# Data_Blue.net
KiCad netlist of a schematic drawn in Altium Designer
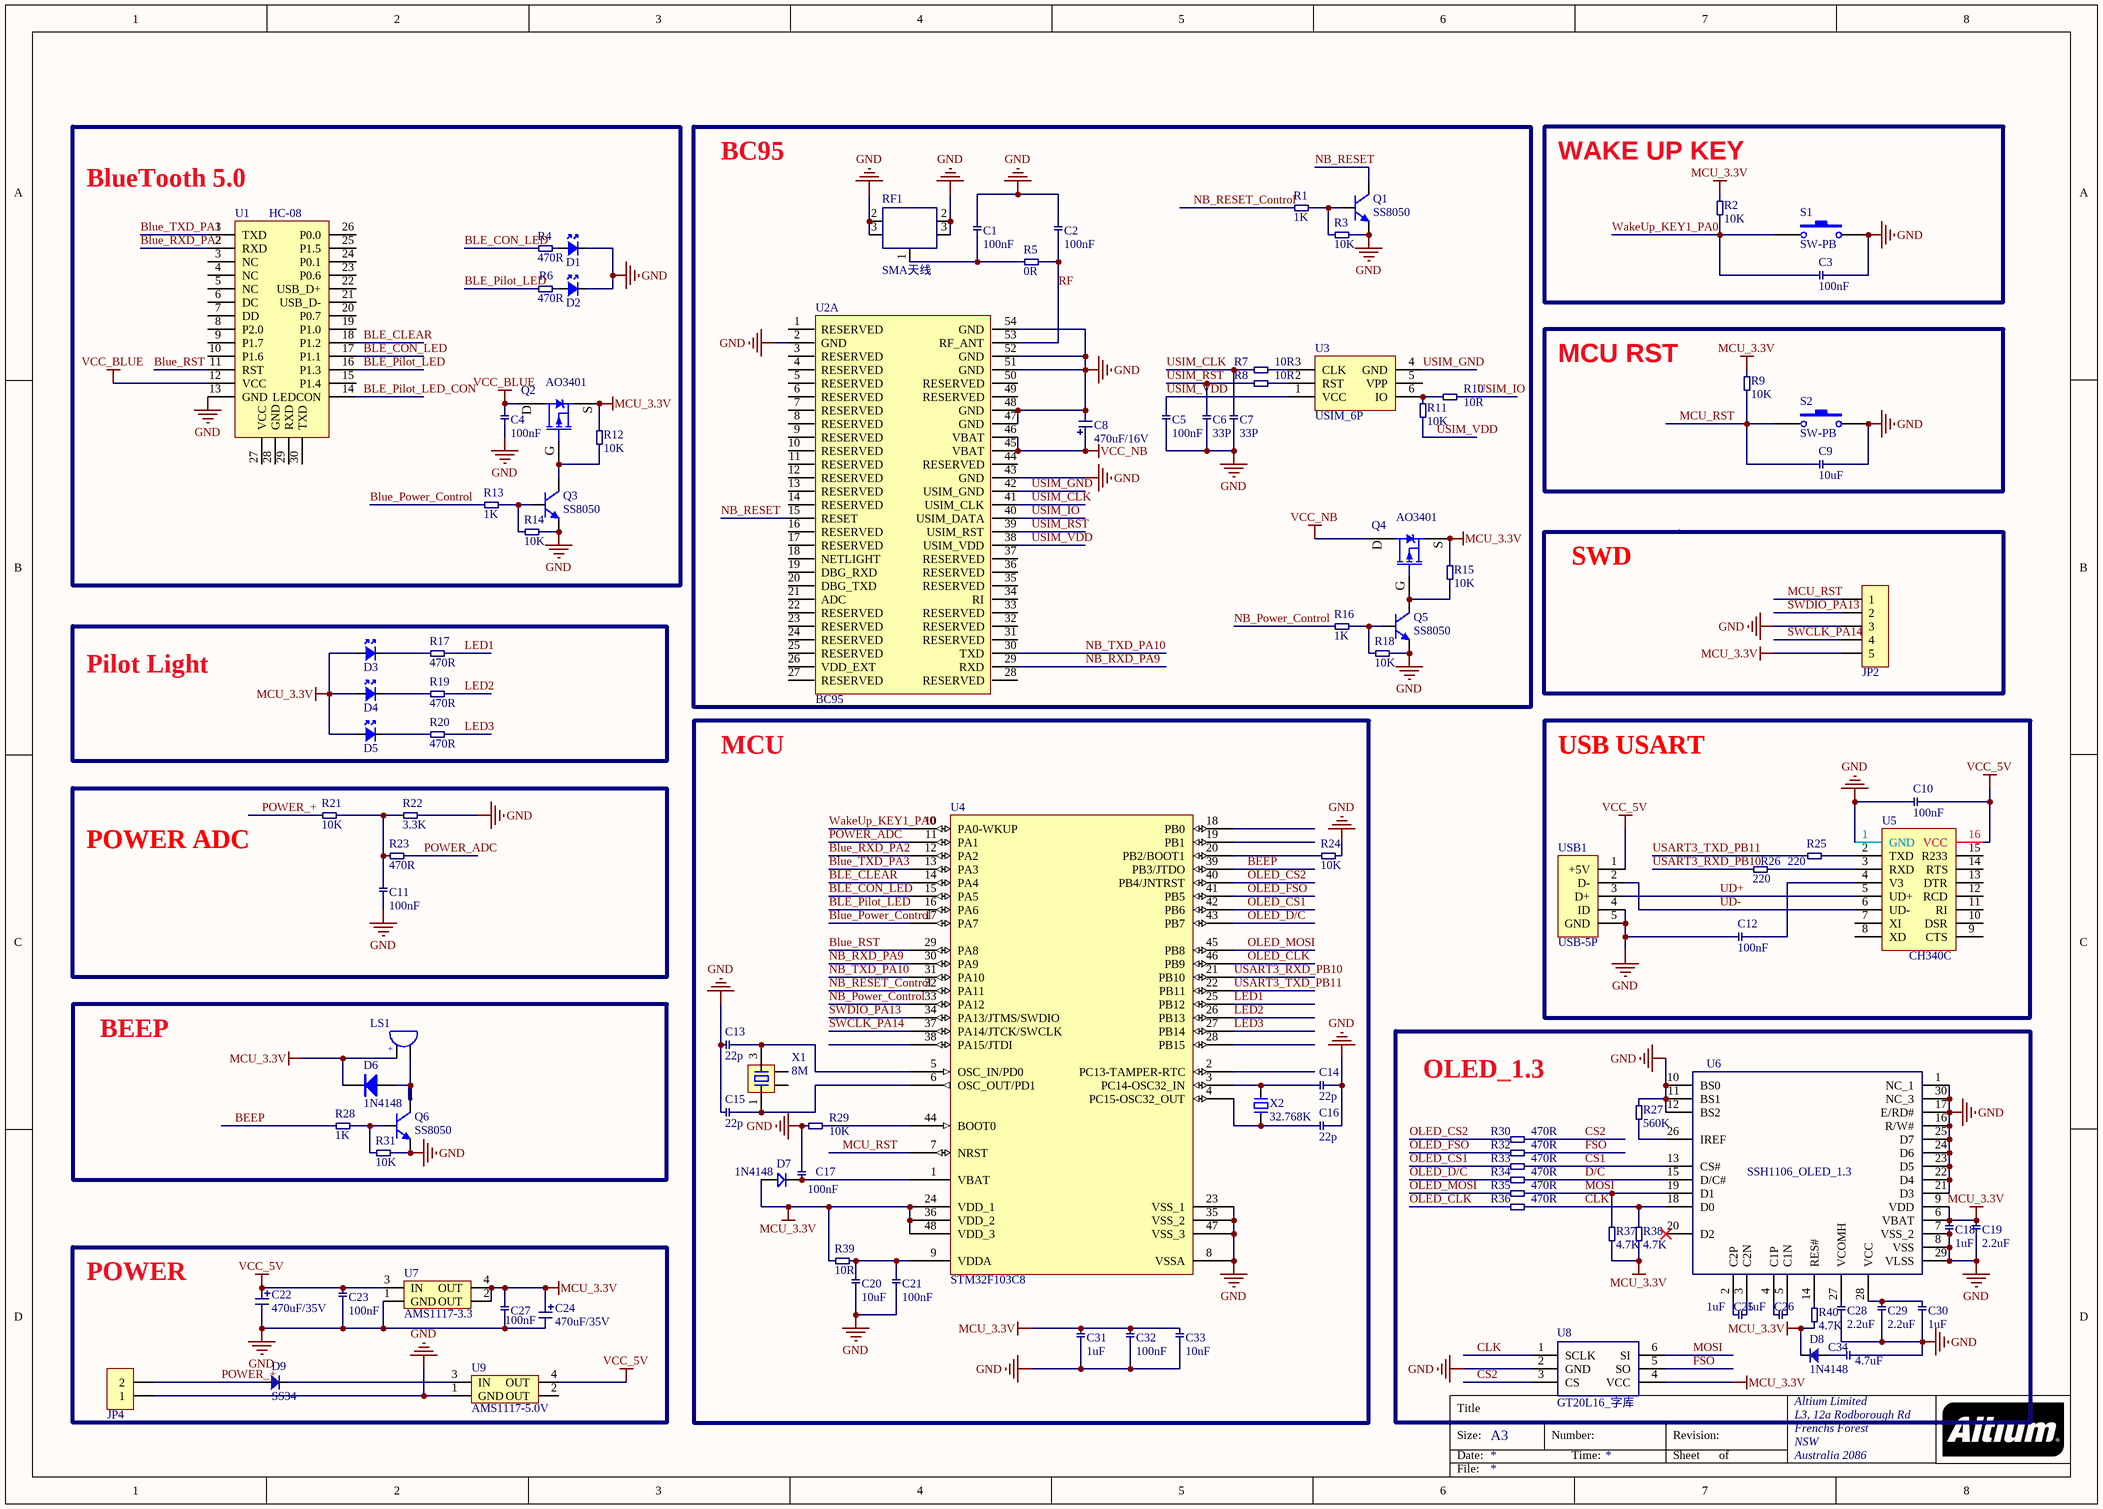
[diagram p0: Data_Blue.SchDoc]

(export (version "E")
  (design (tool "Eeschema 10.0.6"))
  (components
    (comp (ref "C1") (value "100nF") (footprint "0603CC") (libsource (lib "LFZ@WLP") (part "cap")))
    (comp (ref "C2") (value "100nF") (footprint "0603CC") (libsource (lib "LFZ@WLP") (part "cap")))
    (comp (ref "C3") (value "100nF") (footprint "0603CC") (libsource (lib "LFZ@WLP") (part "cap")))
    (comp (ref "C4") (value "100nF") (footprint "0603CC") (libsource (lib "LFZ@WLP") (part "cap")))
    (comp (ref "C5") (value "100nF") (footprint "0603CC") (libsource (lib "LFZ@WLP") (part "cap")))
    (comp (ref "C6") (value "33P") (footprint "0603CC") (libsource (lib "LFZ@WLP") (part "cap")))
    (comp (ref "C7") (value "33P") (footprint "0603CC") (libsource (lib "LFZ@WLP") (part "cap")))
    (comp (ref "C8") (value "470uF/16V") (footprint "C3216") (libsource (lib "LFZ@WLP") (part "Ecap")))
    (comp (ref "C9") (value "10uF") (footprint "0603CC") (libsource (lib "LFZ@WLP") (part "cap")))
    (comp (ref "C10") (value "100nF") (footprint "0603CC") (libsource (lib "LFZ@WLP") (part "cap")))
    (comp (ref "C11") (value "100nF") (footprint "0603CC") (libsource (lib "LFZ@WLP") (part "cap")))
    (comp (ref "C12") (value "100nF") (footprint "0603CC") (libsource (lib "LFZ@WLP") (part "cap")))
    (comp (ref "C13") (value "22p") (footprint "0603CC") (libsource (lib "LFZ@WLP") (part "cap")))
    (comp (ref "C14") (value "22p") (footprint "0603CC") (libsource (lib "LFZ@WLP") (part "cap")))
    (comp (ref "C15") (value "22p") (footprint "0603CC") (libsource (lib "LFZ@WLP") (part "cap")))
    (comp (ref "C16") (value "22p") (footprint "0603CC") (libsource (lib "LFZ@WLP") (part "cap")))
    (comp (ref "C17") (value "100nF") (footprint "0603CC") (libsource (lib "LFZ@WLP") (part "cap")))
    (comp (ref "C18") (value "1uF") (footprint "0603CC") (libsource (lib "LFZ@WLP") (part "cap")))
    (comp (ref "C19") (value "2.2uF") (footprint "0603CC") (libsource (lib "LFZ@WLP") (part "cap")))
    (comp (ref "C20") (value "10uF") (footprint "0603CC") (libsource (lib "LFZ@WLP") (part "cap")))
    (comp (ref "C21") (value "100nF") (footprint "0603CC") (libsource (lib "LFZ@WLP") (part "cap")))
    (comp (ref "C22") (value "470uF/35V") (footprint "CD A(3216)") (libsource (lib "LFZ@WLP") (part "Ecap")))
    (comp (ref "C23") (value "100nF") (footprint "0603CC") (libsource (lib "LFZ@WLP") (part "cap")))
    (comp (ref "C24") (value "470uF/35V") (footprint "C3216") (libsource (lib "LFZ@WLP") (part "Ecap")))
    (comp (ref "C25") (value "1uF") (footprint "0603CC") (libsource (lib "LFZ@WLP") (part "cap")))
    (comp (ref "C26") (value "1uF") (footprint "0603CC") (libsource (lib "LFZ@WLP") (part "cap")))
    (comp (ref "C27") (value "100nF") (footprint "0603CC") (libsource (lib "LFZ@WLP") (part "cap")))
    (comp (ref "C28") (value "2.2uF") (footprint "0603CC") (libsource (lib "LFZ@WLP") (part "cap")))
    (comp (ref "C29") (value "2.2uF") (footprint "0603CC") (libsource (lib "LFZ@WLP") (part "cap")))
    (comp (ref "C30") (value "1uF") (footprint "0603CC") (libsource (lib "LFZ@WLP") (part "cap")))
    (comp (ref "C31") (value "1uF") (footprint "0603CC") (libsource (lib "LFZ@WLP") (part "cap")))
    (comp (ref "C32") (value "100nF") (footprint "0603CC") (libsource (lib "LFZ@WLP") (part "cap")))
    (comp (ref "C33") (value "10nF") (footprint "0603CC") (libsource (lib "LFZ@WLP") (part "cap")))
    (comp (ref "C34") (value "4.7uF") (footprint "0603CC") (libsource (lib "LFZ@WLP") (part "cap")))
    (comp (ref "D1") (value "LED") (footprint "LED 0603G") (libsource (lib "LFZ@WLP") (part "LED")))
    (comp (ref "D2") (value "LED") (footprint "LED 0603R") (libsource (lib "LFZ@WLP") (part "LED")))
    (comp (ref "D3") (value "LED") (footprint "LED 3MM-G") (libsource (lib "LFZ@WLP") (part "LED")))
    (comp (ref "D4") (value "LED") (footprint "LED 3MM-G") (libsource (lib "LFZ@WLP") (part "LED")))
    (comp (ref "D5") (value "LED") (footprint "LED 3MM-G") (libsource (lib "LFZ@WLP") (part "LED")))
    (comp (ref "D6")
      (value "1N4148")
      (footprint "SOD-323")
      (description "高速开关二极管")
      (libsource (lib "8.1   - 二极管-整流桥") (part "1N4148"))
    )
    (comp (ref "D7")
      (value "1N4148")
      (footprint "SOD-323")
      (libsource (lib "WarShip V3 STM32103封装库") (part "D"))
    )
    (comp (ref "D8") (value "1N4148") (footprint "SOD-523") (libsource (lib "LFZ@WLP") (part "Diod")))
    (comp (ref "D9") (value "SS34") (footprint "SMA") (libsource (lib "Diod") (part "Diod")))
    (comp (ref "JP2")
      (value "HDR-1X5")
      (footprint "HDR2.54-LI-5P")
      (description "5P接插件")
      (libsource (lib "4.5   - 接插件-脚距2.54") (part "Header 5"))
    )
    (comp (ref "JP4")
      (value "HDR-1X2")
      (footprint "XH2.54-WI-2P")
      (description "2P接插件")
      (libsource (lib "4.5   - 接插件-脚距2.54") (part "Header 2"))
    )
    (comp (ref "LS1")
      (value "DC5V")
      (footprint "BEEP 5x9x5.5")
      (description "蜂鸣器")
      (libsource (lib "15.1 - 未分类器件") (part "BEEP"))
    )
    (comp (ref "Q1")
      (value "SS8050")
      (footprint "SOT23-3N")
      (description "高频放大-NPN型")
      (libsource (lib "6.2   - 三极管") (part "8050-SMD"))
    )
    (comp (ref "Q2")
      (value "AO3401")
      (footprint "SOT23-3N")
      (description "P沟道场效应管")
      (libsource (lib "6.1   - 场效应管-可控硅") (part "SI2301"))
    )
    (comp (ref "Q3")
      (value "SS8050")
      (footprint "SOT23-3N")
      (description "高频放大-NPN型")
      (libsource (lib "6.2   - 三极管") (part "8050-SMD"))
    )
    (comp (ref "Q4")
      (value "AO3401")
      (footprint "SOT23-3N")
      (description "P沟道场效应管")
      (libsource (lib "6.1   - 场效应管-可控硅") (part "SI2301"))
    )
    (comp (ref "Q5")
      (value "SS8050")
      (footprint "SOT23-3N")
      (description "高频放大-NPN型")
      (libsource (lib "6.2   - 三极管") (part "8050-SMD"))
    )
    (comp (ref "Q6")
      (value "SS8050")
      (footprint "SOT23-3N")
      (description "高频放大-NPN型")
      (libsource (lib "6.2   - 三极管") (part "8050-SMD"))
    )
    (comp (ref "R1") (value "1K") (footprint "0603RR") (libsource (lib "LFZ@WLP") (part "res")))
    (comp (ref "R2") (value "10K") (footprint "0603RR") (libsource (lib "LFZ@WLP") (part "res")))
    (comp (ref "R3") (value "10K") (footprint "0603RR") (libsource (lib "LFZ@WLP") (part "res")))
    (comp (ref "R4") (value "470R") (footprint "0603RR") (libsource (lib "LFZ@WLP") (part "res")))
    (comp (ref "R5") (value "0R") (footprint "0603RR") (libsource (lib "LFZ@WLP") (part "res")))
    (comp (ref "R6") (value "470R") (footprint "0603RR") (libsource (lib "LFZ@WLP") (part "res")))
    (comp (ref "R7") (value "10R") (footprint "0603RR") (libsource (lib "LFZ@WLP") (part "res")))
    (comp (ref "R8") (value "10R") (footprint "0603RR") (libsource (lib "LFZ@WLP") (part "res")))
    (comp (ref "R9") (value "10K") (footprint "0603RR") (libsource (lib "LFZ@WLP") (part "res")))
    (comp (ref "R10") (value "10R") (footprint "0603RR") (libsource (lib "LFZ@WLP") (part "res")))
    (comp (ref "R11") (value "10K") (footprint "0603RR") (libsource (lib "LFZ@WLP") (part "res")))
    (comp (ref "R12") (value "10K") (footprint "0603RR") (libsource (lib "LFZ@WLP") (part "res")))
    (comp (ref "R13") (value "1K") (footprint "0603RR") (libsource (lib "LFZ@WLP") (part "res")))
    (comp (ref "R14") (value "10K") (footprint "0603RR") (libsource (lib "LFZ@WLP") (part "res")))
    (comp (ref "R15") (value "10K") (footprint "0603RR") (libsource (lib "LFZ@WLP") (part "res")))
    (comp (ref "R16") (value "1K") (footprint "0603RR") (libsource (lib "LFZ@WLP") (part "res")))
    (comp (ref "R17") (value "470R") (footprint "0603RR") (libsource (lib "LFZ@WLP") (part "res")))
    (comp (ref "R18") (value "10K") (footprint "0603RR") (libsource (lib "LFZ@WLP") (part "res")))
    (comp (ref "R19") (value "470R") (footprint "0603RR") (libsource (lib "LFZ@WLP") (part "res")))
    (comp (ref "R20") (value "470R") (footprint "0603RR") (libsource (lib "LFZ@WLP") (part "res")))
    (comp (ref "R21") (value "10K") (footprint "0603RR") (libsource (lib "LFZ@WLP") (part "res")))
    (comp (ref "R22") (value "3.3K") (footprint "0603RR") (libsource (lib "LFZ@WLP") (part "res")))
    (comp (ref "R23") (value "470R") (footprint "0603RR") (libsource (lib "LFZ@WLP") (part "res")))
    (comp (ref "R24") (value "10K") (footprint "0603RR") (libsource (lib "LFZ@WLP") (part "res")))
    (comp (ref "R25") (value "220") (footprint "0603RR") (libsource (lib "LFZ@WLP") (part "res")))
    (comp (ref "R26") (value "220") (footprint "0603RR") (libsource (lib "LFZ@WLP") (part "res")))
    (comp (ref "R27") (value "560K") (footprint "0603RR") (libsource (lib "LFZ@WLP") (part "res")))
    (comp (ref "R28") (value "1K") (footprint "0603RR") (libsource (lib "LFZ@WLP") (part "res")))
    (comp (ref "R29") (value "10K") (footprint "0603RR") (libsource (lib "LFZ@WLP") (part "res")))
    (comp (ref "R30") (value "470R") (footprint "0603RR") (libsource (lib "LFZ@WLP") (part "res")))
    (comp (ref "R31") (value "10K") (footprint "0603RR") (libsource (lib "LFZ@WLP") (part "res")))
    (comp (ref "R32") (value "470R") (footprint "0603RR") (libsource (lib "LFZ@WLP") (part "res")))
    (comp (ref "R33") (value "470R") (footprint "0603RR") (libsource (lib "LFZ@WLP") (part "res")))
    (comp (ref "R34") (value "470R") (footprint "0603RR") (libsource (lib "LFZ@WLP") (part "res")))
    (comp (ref "R35") (value "470R") (footprint "0603RR") (libsource (lib "LFZ@WLP") (part "res")))
    (comp (ref "R36") (value "470R") (footprint "0603RR") (libsource (lib "LFZ@WLP") (part "res")))
    (comp (ref "R37") (value "4.7K") (footprint "0603RR") (libsource (lib "LFZ@WLP") (part "res")))
    (comp (ref "R38") (value "4.7K") (footprint "0603RR") (libsource (lib "LFZ@WLP") (part "res")))
    (comp (ref "R39") (value "10R") (footprint "0603RR") (libsource (lib "LFZ@WLP") (part "res")))
    (comp (ref "R40") (value "4.7K") (footprint "0603RR") (libsource (lib "LFZ@WLP") (part "res")))
    (comp (ref "RF1") (value "SMA天线") (footprint "SMA_FR") (libsource (lib "LFZ@WLP") (part "SMA天线")))
    (comp (ref "S1")
      (value "SW-PB")
      (footprint "TSW SMD-6*6*6")
      (description "Switch")
      (libsource (lib "开关及电源") (part "SW-PB"))
    )
    (comp (ref "S2")
      (value "SW-PB")
      (footprint "TSW SMD-4*4*1.5")
      (description "Switch")
      (libsource (lib "开关及电源") (part "SW-PB"))
    )
    (comp (ref "U1") (value "HC-08") (footprint "HC-08") (libsource (lib "LFZ@WLP") (part "HC-08")))
    (comp (ref "U2")
      (value "BC95")
      (footprint "BC95")
      (libsource (lib "Quectel_BC95_SCH_Part_Protel&AD_20170925") (part "BC95"))
    )
    (comp (ref "U3") (value "USIM_6P") (footprint "SIM 6P 自弹") (libsource (lib "XG-BM02") (part "USIM-6P")))
    (comp (ref "U4")
      (value "STM32F103C8")
      (footprint "LQFP48 7X7_M")
      (description "Flaah:64/RAM:20/IO:36")
      (libsource (lib "2.1   - STM32系列单片机") (part "STM32F103C8"))
    )
    (comp (ref "U5") (value "CH340C") (footprint "SOP16_L") (libsource (lib "LFZ@WLP") (part "CH340C")))
    (comp (ref "U6")
      (value "SSH1106_OLED_1.3")
      (footprint "OLED_1.3_FPC_30")
      (libsource (lib "LFZ@WLP") (part "SSH1106_OLED_1.3"))
    )
    (comp (ref "U7")
      (value "AMS1117-3.3")
      (footprint "SOT223_N")
      (libsource (lib "WarShip V3 STM32103封装库") (part "AMS1117"))
    )
    (comp (ref "U8")
      (value "GT20L16_字库")
      (footprint "SOT23-6")
      (libsource (lib "LFZ@WLP") (part "GT20L16_字库"))
    )
    (comp (ref "U9")
      (value "AMS1117-5.0V")
      (footprint "SOT223_N")
      (libsource (lib "WarShip V3 STM32103封装库") (part "AMS1117"))
    )
    (comp (ref "USB1")
      (value "USB-5P")
      (footprint "USB-MICRO_A")
      (description "微型USB母座")
      (libsource (lib "4.1   - 接口类") (part "USB-5P"))
    )
    (comp (ref "X1")
      (value "8M")
      (footprint "OSC 3225-4P")
      (description "4脚无源晶振")
      (libsource (lib "10.1 - 保险丝-晶振") (part "XTAL-4P"))
    )
    (comp (ref "X2")
      (value "32.768K")
      (footprint "OSC 3215-2P")
      (description "2脚无源脚晶振")
      (libsource (lib "10.1 - 保险丝-晶振") (part "XTAL-2P"))
    )
  )
  (nets
    (net (code "1") (name "/BEEP") (class "Default")
      (node (ref "R28") (pin "1") (pinfunction "1_1") (pintype "passive"))
      (node (ref "U4") (pin "39") (pinfunction "PB3/JTDO_39") (pintype "bidirectional"))
    )
    (net (code "2") (name "/BLE_CLEAR") (class "Default")
      (node (ref "U1") (pin "18") (pinfunction "P1.2_18") (pintype "passive"))
      (node (ref "U4") (pin "14") (pinfunction "PA4_14") (pintype "bidirectional"))
    )
    (net (code "3") (name "/BLE_CON_LED") (class "Default")
      (node (ref "R4") (pin "1") (pinfunction "1_1") (pintype "passive"))
      (node (ref "U1") (pin "17") (pinfunction "P1.1_17") (pintype "passive"))
      (node (ref "U4") (pin "15") (pinfunction "PA5_15") (pintype "bidirectional"))
    )
    (net (code "4") (name "/BLE_Pilot_LED") (class "Default")
      (node (ref "R6") (pin "1") (pinfunction "1_1") (pintype "passive"))
      (node (ref "U1") (pin "16") (pinfunction "P1.3_16") (pintype "passive"))
      (node (ref "U4") (pin "16") (pinfunction "PA6_16") (pintype "bidirectional"))
    )
    (net (code "5") (name "/BLE_Pilot_LED_CON") (class "Default")
      (node (ref "U1") (pin "14") (pinfunction "LEDCON_14") (pintype "passive"))
    )
    (net (code "6") (name "/Blue_Power_Control") (class "Default")
      (node (ref "R13") (pin "1") (pinfunction "1_1") (pintype "passive"))
      (node (ref "U4") (pin "17") (pinfunction "PA7_17") (pintype "bidirectional"))
    )
    (net (code "7") (name "/Blue_RST") (class "Default")
      (node (ref "U1") (pin "11") (pinfunction "RST_11") (pintype "passive"))
      (node (ref "U4") (pin "29") (pinfunction "PA8_29") (pintype "bidirectional"))
    )
    (net (code "8") (name "/Blue_RXD_PA2") (class "Default")
      (node (ref "U1") (pin "2") (pinfunction "RXD_2") (pintype "passive"))
      (node (ref "U4") (pin "12") (pinfunction "PA2_12") (pintype "bidirectional"))
    )
    (net (code "9") (name "/Blue_TXD_PA3") (class "Default")
      (node (ref "U1") (pin "1") (pinfunction "TXD_1") (pintype "passive"))
      (node (ref "U4") (pin "13") (pinfunction "PA3_13") (pintype "bidirectional"))
    )
    (net (code "10") (name "/CLK") (class "Default")
      (node (ref "R36") (pin "2") (pinfunction "2_2") (pintype "passive"))
      (node (ref "R38") (pin "2") (pinfunction "2_2") (pintype "passive"))
      (node (ref "U6") (pin "18") (pinfunction "D0_18") (pintype "passive"))
      (node (ref "U8") (pin "1") (pinfunction "SCLK_1") (pintype "passive"))
    )
    (net (code "11") (name "/CS1") (class "Default")
      (node (ref "R33") (pin "2") (pinfunction "2_2") (pintype "passive"))
      (node (ref "U6") (pin "13") (pinfunction "CS#_13") (pintype "passive"))
    )
    (net (code "12") (name "/CS2") (class "Default")
      (node (ref "R30") (pin "2") (pinfunction "2_2") (pintype "passive"))
      (node (ref "U8") (pin "3") (pinfunction "CS_3") (pintype "passive"))
    )
    (net (code "13") (name "/D{slash}C") (class "Default")
      (node (ref "R34") (pin "2") (pinfunction "2_2") (pintype "passive"))
      (node (ref "U6") (pin "15") (pinfunction "D/C#_15") (pintype "passive"))
    )
    (net (code "14") (name "/FSO") (class "Default")
      (node (ref "R32") (pin "2") (pinfunction "2_2") (pintype "passive"))
      (node (ref "U8") (pin "5") (pinfunction "SO_5") (pintype "passive"))
    )
    (net (code "15") (name "/LED1") (class "Default")
      (node (ref "R17") (pin "2") (pinfunction "2_2") (pintype "passive"))
      (node (ref "U4") (pin "25") (pinfunction "PB12_25") (pintype "bidirectional"))
    )
    (net (code "16") (name "/LED2") (class "Default")
      (node (ref "R19") (pin "2") (pinfunction "2_2") (pintype "passive"))
      (node (ref "U4") (pin "26") (pinfunction "PB13_26") (pintype "bidirectional"))
    )
    (net (code "17") (name "/LED3") (class "Default")
      (node (ref "R20") (pin "2") (pinfunction "2_2") (pintype "passive"))
      (node (ref "U4") (pin "27") (pinfunction "PB14_27") (pintype "bidirectional"))
    )
    (net (code "18") (name "/MCU_RST") (class "Default")
      (node (ref "C9") (pin "2") (pinfunction "2_2") (pintype "passive"))
      (node (ref "JP2") (pin "1") (pinfunction "1_1") (pintype "passive"))
      (node (ref "R9") (pin "1") (pinfunction "1_1") (pintype "passive"))
      (node (ref "S2") (pin "1") (pinfunction "1_1") (pintype "passive"))
      (node (ref "U4") (pin "7") (pinfunction "NRST_7") (pintype "bidirectional"))
    )
    (net (code "19") (name "/MOSI") (class "Default")
      (node (ref "R35") (pin "2") (pinfunction "2_2") (pintype "passive"))
      (node (ref "R37") (pin "2") (pinfunction "2_2") (pintype "passive"))
      (node (ref "U6") (pin "19") (pinfunction "D1_19") (pintype "passive"))
      (node (ref "U8") (pin "6") (pinfunction "SI_6") (pintype "passive"))
    )
    (net (code "20") (name "/NB_Power_Control") (class "Default")
      (node (ref "R16") (pin "1") (pinfunction "1_1") (pintype "passive"))
      (node (ref "U4") (pin "33") (pinfunction "PA12_33") (pintype "bidirectional"))
    )
    (net (code "21") (name "/NB_RESET") (class "Default")
      (node (ref "Q1") (pin "3") (pinfunction "C_3") (pintype "passive"))
      (node (ref "U2") (pin "15") (pinfunction "RESET_15") (pintype "passive"))
    )
    (net (code "22") (name "/NB_RESET_Control") (class "Default")
      (node (ref "R1") (pin "1") (pinfunction "1_1") (pintype "passive"))
      (node (ref "U4") (pin "32") (pinfunction "PA11_32") (pintype "bidirectional"))
    )
    (net (code "23") (name "/NB_RXD_PA9") (class "Default")
      (node (ref "U2") (pin "29") (pinfunction "RXD_29") (pintype "passive"))
      (node (ref "U4") (pin "30") (pinfunction "PA9_30") (pintype "bidirectional"))
    )
    (net (code "24") (name "/NB_TXD_PA10") (class "Default")
      (node (ref "U2") (pin "30") (pinfunction "TXD_30") (pintype "passive"))
      (node (ref "U4") (pin "31") (pinfunction "PA10_31") (pintype "bidirectional"))
    )
    (net (code "25") (name "/OLED_CLK") (class "Default")
      (node (ref "R36") (pin "1") (pinfunction "1_1") (pintype "passive"))
      (node (ref "U4") (pin "46") (pinfunction "PB9_46") (pintype "bidirectional"))
    )
    (net (code "26") (name "/OLED_CS1") (class "Default")
      (node (ref "R33") (pin "1") (pinfunction "1_1") (pintype "passive"))
      (node (ref "U4") (pin "42") (pinfunction "PB6_42") (pintype "bidirectional"))
    )
    (net (code "27") (name "/OLED_CS2") (class "Default")
      (node (ref "R30") (pin "1") (pinfunction "1_1") (pintype "passive"))
      (node (ref "U4") (pin "40") (pinfunction "PB4/JNTRST_40") (pintype "bidirectional"))
    )
    (net (code "28") (name "/OLED_D{slash}C") (class "Default")
      (node (ref "R34") (pin "1") (pinfunction "1_1") (pintype "passive"))
      (node (ref "U4") (pin "43") (pinfunction "PB7_43") (pintype "bidirectional"))
    )
    (net (code "29") (name "/OLED_FSO") (class "Default")
      (node (ref "R32") (pin "1") (pinfunction "1_1") (pintype "passive"))
      (node (ref "U4") (pin "41") (pinfunction "PB5_41") (pintype "bidirectional"))
    )
    (net (code "30") (name "/OLED_MOSI") (class "Default")
      (node (ref "R35") (pin "1") (pinfunction "1_1") (pintype "passive"))
      (node (ref "U4") (pin "45") (pinfunction "PB8_45") (pintype "bidirectional"))
    )
    (net (code "31") (name "/POWER_+") (class "Default")
      (node (ref "D9") (pin "1") (pinfunction "ANODE_1") (pintype "passive"))
      (node (ref "JP4") (pin "2") (pinfunction "2_2") (pintype "passive"))
      (node (ref "R21") (pin "1") (pinfunction "1_1") (pintype "passive"))
    )
    (net (code "32") (name "/POWER_ADC") (class "Default")
      (node (ref "R23") (pin "1") (pinfunction "1_1") (pintype "passive"))
      (node (ref "U4") (pin "11") (pinfunction "PA1_11") (pintype "bidirectional"))
    )
    (net (code "33") (name "/RF") (class "Default")
      (node (ref "C2") (pin "1") (pinfunction "1_1") (pintype "passive"))
      (node (ref "R5") (pin "1") (pinfunction "1_1") (pintype "passive"))
      (node (ref "U2") (pin "53") (pinfunction "RF_ANT_53") (pintype "passive"))
    )
    (net (code "34") (name "/SWCLK_PA14") (class "Default")
      (node (ref "JP2") (pin "4") (pinfunction "4_4") (pintype "passive"))
      (node (ref "U4") (pin "37") (pinfunction "PA14/JTCK/SWCLK_37") (pintype "bidirectional"))
    )
    (net (code "35") (name "/SWDIO_PA13") (class "Default")
      (node (ref "JP2") (pin "2") (pinfunction "2_2") (pintype "passive"))
      (node (ref "U4") (pin "34") (pinfunction "PA13/JTMS/SWDIO_34") (pintype "bidirectional"))
    )
    (net (code "36") (name "/UD+") (class "Default")
      (node (ref "U5") (pin "5") (pinfunction "UD+_5") (pintype "passive"))
      (node (ref "USB1") (pin "3") (pinfunction "D+_3") (pintype "passive"))
    )
    (net (code "37") (name "/UD-") (class "Default")
      (node (ref "U5") (pin "6") (pinfunction "UD-_6") (pintype "passive"))
      (node (ref "USB1") (pin "2") (pinfunction "D-_2") (pintype "passive"))
    )
    (net (code "38") (name "/USART3_RXD_PB10") (class "Default")
      (node (ref "R26") (pin "1") (pinfunction "1_1") (pintype "passive"))
      (node (ref "U4") (pin "21") (pinfunction "PB10_21") (pintype "bidirectional"))
    )
    (net (code "39") (name "/USART3_TXD_PB11") (class "Default")
      (node (ref "R25") (pin "1") (pinfunction "1_1") (pintype "passive"))
      (node (ref "U4") (pin "22") (pinfunction "PB11_22") (pintype "bidirectional"))
    )
    (net (code "40") (name "/USIM_CLK") (class "Default")
      (node (ref "C7") (pin "2") (pinfunction "2_2") (pintype "passive"))
      (node (ref "R7") (pin "1") (pinfunction "1_1") (pintype "passive"))
      (node (ref "U2") (pin "41") (pinfunction "USIM_CLK_41") (pintype "passive"))
    )
    (net (code "41") (name "/USIM_GND") (class "Default")
      (node (ref "U2") (pin "42") (pinfunction "USIM_GND_42") (pintype "passive"))
      (node (ref "U3") (pin "4") (pinfunction "GND_4") (pintype "passive"))
    )
    (net (code "42") (name "/USIM_IO") (class "Default")
      (node (ref "R10") (pin "1") (pinfunction "1_1") (pintype "passive"))
      (node (ref "U2") (pin "40") (pinfunction "USIM_DATA_40") (pintype "passive"))
    )
    (net (code "43") (name "/USIM_RST") (class "Default")
      (node (ref "C6") (pin "2") (pinfunction "2_2") (pintype "passive"))
      (node (ref "R8") (pin "1") (pinfunction "1_1") (pintype "passive"))
      (node (ref "U2") (pin "39") (pinfunction "USIM_RST_39") (pintype "passive"))
    )
    (net (code "44") (name "/USIM_VDD") (class "Default")
      (node (ref "C5") (pin "2") (pinfunction "2_2") (pintype "passive"))
      (node (ref "R11") (pin "1") (pinfunction "1_1") (pintype "passive"))
      (node (ref "U2") (pin "38") (pinfunction "USIM_VDD_38") (pintype "passive"))
      (node (ref "U3") (pin "1") (pinfunction "VCC_1") (pintype "passive"))
    )
    (net (code "45") (name "/WakeUp_KEY1_PA0") (class "Default")
      (node (ref "C3") (pin "1") (pinfunction "1_1") (pintype "passive"))
      (node (ref "R2") (pin "1") (pinfunction "1_1") (pintype "passive"))
      (node (ref "S1") (pin "1") (pinfunction "1_1") (pintype "passive"))
      (node (ref "U4") (pin "10") (pinfunction "PA0-WKUP_10") (pintype "bidirectional"))
    )
    (net (code "46") (name "GND") (class "Default")
      (node (ref "C1") (pin "2") (pinfunction "2_2") (pintype "passive"))
      (node (ref "C10") (pin "2") (pinfunction "2_2") (pintype "passive"))
      (node (ref "C11") (pin "1") (pinfunction "1_1") (pintype "passive"))
      (node (ref "C12") (pin "2") (pinfunction "2_2") (pintype "passive"))
      (node (ref "C13") (pin "1") (pinfunction "1_1") (pintype "passive"))
      (node (ref "C14") (pin "2") (pinfunction "2_2") (pintype "passive"))
      (node (ref "C15") (pin "1") (pinfunction "1_1") (pintype "passive"))
      (node (ref "C16") (pin "2") (pinfunction "2_2") (pintype "passive"))
      (node (ref "C17") (pin "2") (pinfunction "2_2") (pintype "passive"))
      (node (ref "C18") (pin "1") (pinfunction "1_1") (pintype "passive"))
      (node (ref "C19") (pin "1") (pinfunction "1_1") (pintype "passive"))
      (node (ref "C2") (pin "2") (pinfunction "2_2") (pintype "passive"))
      (node (ref "C20") (pin "1") (pinfunction "1_1") (pintype "passive"))
      (node (ref "C21") (pin "1") (pinfunction "1_1") (pintype "passive"))
      (node (ref "C22") (pin "2") (pinfunction "2_2") (pintype "passive"))
      (node (ref "C23") (pin "1") (pinfunction "1_1") (pintype "passive"))
      (node (ref "C24") (pin "2") (pinfunction "2_2") (pintype "passive"))
      (node (ref "C27") (pin "1") (pinfunction "1_1") (pintype "passive"))
      (node (ref "C28") (pin "1") (pinfunction "1_1") (pintype "passive"))
      (node (ref "C29") (pin "1") (pinfunction "1_1") (pintype "passive"))
      (node (ref "C3") (pin "2") (pinfunction "2_2") (pintype "passive"))
      (node (ref "C30") (pin "1") (pinfunction "1_1") (pintype "passive"))
      (node (ref "C31") (pin "1") (pinfunction "1_1") (pintype "passive"))
      (node (ref "C32") (pin "1") (pinfunction "1_1") (pintype "passive"))
      (node (ref "C33") (pin "1") (pinfunction "1_1") (pintype "passive"))
      (node (ref "C34") (pin "1") (pinfunction "1_1") (pintype "passive"))
      (node (ref "C4") (pin "1") (pinfunction "1_1") (pintype "passive"))
      (node (ref "C5") (pin "1") (pinfunction "1_1") (pintype "passive"))
      (node (ref "C6") (pin "1") (pinfunction "1_1") (pintype "passive"))
      (node (ref "C7") (pin "1") (pinfunction "1_1") (pintype "passive"))
      (node (ref "C8") (pin "2") (pinfunction "2_2") (pintype "passive"))
      (node (ref "C9") (pin "1") (pinfunction "1_1") (pintype "passive"))
      (node (ref "D1") (pin "2") (pinfunction "CATHODE_2") (pintype "passive"))
      (node (ref "D2") (pin "2") (pinfunction "CATHODE_2") (pintype "passive"))
      (node (ref "JP2") (pin "3") (pinfunction "3_3") (pintype "passive"))
      (node (ref "JP4") (pin "1") (pinfunction "1_1") (pintype "passive"))
      (node (ref "Q1") (pin "2") (pinfunction "E_2") (pintype "passive"))
      (node (ref "Q3") (pin "2") (pinfunction "E_2") (pintype "passive"))
      (node (ref "Q5") (pin "2") (pinfunction "E_2") (pintype "passive"))
      (node (ref "Q6") (pin "2") (pinfunction "E_2") (pintype "passive"))
      (node (ref "R14") (pin "2") (pinfunction "2_2") (pintype "passive"))
      (node (ref "R18") (pin "2") (pinfunction "2_2") (pintype "passive"))
      (node (ref "R22") (pin "2") (pinfunction "2_2") (pintype "passive"))
      (node (ref "R24") (pin "2") (pinfunction "2_2") (pintype "passive"))
      (node (ref "R27") (pin "2") (pinfunction "2_2") (pintype "passive"))
      (node (ref "R29") (pin "1") (pinfunction "1_1") (pintype "passive"))
      (node (ref "R3") (pin "2") (pinfunction "2_2") (pintype "passive"))
      (node (ref "R31") (pin "2") (pinfunction "2_2") (pintype "passive"))
      (node (ref "RF1") (pin "2") (pinfunction "2_2") (pintype "passive"))
      (node (ref "RF1") (pin "3") (pinfunction "3_3") (pintype "passive"))
      (node (ref "S1") (pin "2") (pinfunction "2_2") (pintype "passive"))
      (node (ref "S2") (pin "2") (pinfunction "2_2") (pintype "passive"))
      (node (ref "U1") (pin "13") (pinfunction "GND_13") (pintype "passive"))
      (node (ref "U2") (pin "2") (pinfunction "GND_2") (pintype "passive"))
      (node (ref "U2") (pin "43") (pinfunction "GND_43") (pintype "passive"))
      (node (ref "U2") (pin "47") (pinfunction "GND_47") (pintype "passive"))
      (node (ref "U2") (pin "48") (pinfunction "GND_48") (pintype "passive"))
      (node (ref "U2") (pin "51") (pinfunction "GND_51") (pintype "passive"))
      (node (ref "U2") (pin "52") (pinfunction "GND_52") (pintype "passive"))
      (node (ref "U2") (pin "54") (pinfunction "GND_54") (pintype "passive"))
      (node (ref "U4") (pin "23") (pinfunction "VSS_1_23") (pintype "power_in"))
      (node (ref "U4") (pin "35") (pinfunction "VSS_2_35") (pintype "power_in"))
      (node (ref "U4") (pin "47") (pinfunction "VSS_3_47") (pintype "power_in"))
      (node (ref "U4") (pin "8") (pinfunction "VSSA_8") (pintype "power_in"))
      (node (ref "U5") (pin "1") (pinfunction "GND_1") (pintype "passive"))
      (node (ref "U6") (pin "1") (pinfunction "NC_1_1") (pintype "passive"))
      (node (ref "U6") (pin "10") (pinfunction "BS0_10") (pintype "passive"))
      (node (ref "U6") (pin "11") (pinfunction "BS1_11") (pintype "passive"))
      (node (ref "U6") (pin "12") (pinfunction "BS2_12") (pintype "passive"))
      (node (ref "U6") (pin "16") (pinfunction "R/W#_16") (pintype "passive"))
      (node (ref "U6") (pin "17") (pinfunction "E/RD#_17") (pintype "passive"))
      (node (ref "U6") (pin "21") (pinfunction "D3_21") (pintype "passive"))
      (node (ref "U6") (pin "22") (pinfunction "D4_22") (pintype "passive"))
      (node (ref "U6") (pin "23") (pinfunction "D5_23") (pintype "passive"))
      (node (ref "U6") (pin "24") (pinfunction "D6_24") (pintype "passive"))
      (node (ref "U6") (pin "25") (pinfunction "D7_25") (pintype "passive"))
      (node (ref "U6") (pin "29") (pinfunction "VLSS_29") (pintype "passive"))
      (node (ref "U6") (pin "30") (pinfunction "NC_3_30") (pintype "passive"))
      (node (ref "U6") (pin "7") (pinfunction "VSS_2_7") (pintype "passive"))
      (node (ref "U6") (pin "8") (pinfunction "VSS_8") (pintype "passive"))
      (node (ref "U7") (pin "1") (pinfunction "GND_1") (pintype "passive"))
      (node (ref "U8") (pin "2") (pinfunction "GND_2") (pintype "passive"))
      (node (ref "U9") (pin "1") (pinfunction "GND_1") (pintype "passive"))
      (node (ref "USB1") (pin "4") (pinfunction "ID_4") (pintype "passive"))
      (node (ref "USB1") (pin "5") (pinfunction "GND_5") (pintype "passive"))
    )
    (net (code "47") (name "MCU_3.3V") (class "Default")
      (node (ref "C18") (pin "2") (pinfunction "2_2") (pintype "passive"))
      (node (ref "C19") (pin "2") (pinfunction "2_2") (pintype "passive"))
      (node (ref "C24") (pin "1") (pinfunction "1_1") (pintype "passive"))
      (node (ref "C27") (pin "2") (pinfunction "2_2") (pintype "passive"))
      (node (ref "C31") (pin "2") (pinfunction "2_2") (pintype "passive"))
      (node (ref "C32") (pin "2") (pinfunction "2_2") (pintype "passive"))
      (node (ref "C33") (pin "2") (pinfunction "2_2") (pintype "passive"))
      (node (ref "D3") (pin "1") (pinfunction "ANODE_1") (pintype "passive"))
      (node (ref "D4") (pin "1") (pinfunction "ANODE_1") (pintype "passive"))
      (node (ref "D5") (pin "1") (pinfunction "ANODE_1") (pintype "passive"))
      (node (ref "D6") (pin "2") (pinfunction "K_2") (pintype "passive"))
      (node (ref "D7") (pin "1") (pintype "passive"))
      (node (ref "D8") (pin "2") (pinfunction "CATHODE_2") (pintype "passive"))
      (node (ref "JP2") (pin "5") (pinfunction "5_5") (pintype "passive"))
      (node (ref "LS1") (pin "1") (pinfunction "1_1") (pintype "passive"))
      (node (ref "Q2") (pin "2") (pinfunction "S_2") (pintype "passive"))
      (node (ref "Q4") (pin "2") (pinfunction "S_2") (pintype "passive"))
      (node (ref "R12") (pin "2") (pinfunction "2_2") (pintype "passive"))
      (node (ref "R15") (pin "2") (pinfunction "2_2") (pintype "passive"))
      (node (ref "R2") (pin "2") (pinfunction "2_2") (pintype "passive"))
      (node (ref "R37") (pin "1") (pinfunction "1_1") (pintype "passive"))
      (node (ref "R38") (pin "1") (pinfunction "1_1") (pintype "passive"))
      (node (ref "R39") (pin "1") (pinfunction "1_1") (pintype "passive"))
      (node (ref "R40") (pin "2") (pinfunction "2_2") (pintype "passive"))
      (node (ref "R9") (pin "2") (pinfunction "2_2") (pintype "passive"))
      (node (ref "U4") (pin "24") (pinfunction "VDD_1_24") (pintype "power_in"))
      (node (ref "U4") (pin "36") (pinfunction "VDD_2_36") (pintype "power_in"))
      (node (ref "U4") (pin "48") (pinfunction "VDD_3_48") (pintype "power_in"))
      (node (ref "U6") (pin "6") (pinfunction "VBAT_6") (pintype "passive"))
      (node (ref "U6") (pin "9") (pinfunction "VDD_9") (pintype "passive"))
      (node (ref "U7") (pin "2") (pinfunction "OUT_2") (pintype "passive"))
      (node (ref "U7") (pin "4") (pinfunction "OUT_4") (pintype "passive"))
      (node (ref "U8") (pin "4") (pinfunction "VCC_4") (pintype "passive"))
    )
    (net (code "48") (name "Net-(C1-Pad1)") (class "Default")
      (node (ref "C1") (pin "1") (pinfunction "1_1") (pintype "passive"))
      (node (ref "R5") (pin "2") (pinfunction "2_2") (pintype "passive"))
      (node (ref "RF1") (pin "1") (pinfunction "1_1") (pintype "passive"))
    )
    (net (code "49") (name "Net-(C11-Pad2)") (class "Default")
      (node (ref "C11") (pin "2") (pinfunction "2_2") (pintype "passive"))
      (node (ref "R21") (pin "2") (pinfunction "2_2") (pintype "passive"))
      (node (ref "R22") (pin "1") (pinfunction "1_1") (pintype "passive"))
      (node (ref "R23") (pin "2") (pinfunction "2_2") (pintype "passive"))
    )
    (net (code "50") (name "Net-(D1-ANODE)") (class "Default")
      (node (ref "D1") (pin "1") (pinfunction "ANODE_1") (pintype "passive"))
      (node (ref "R4") (pin "2") (pinfunction "2_2") (pintype "passive"))
    )
    (net (code "51") (name "Net-(D2-ANODE)") (class "Default")
      (node (ref "D2") (pin "1") (pinfunction "ANODE_1") (pintype "passive"))
      (node (ref "R6") (pin "2") (pinfunction "2_2") (pintype "passive"))
    )
    (net (code "52") (name "Net-(D3-CATHODE)") (class "Default")
      (node (ref "D3") (pin "2") (pinfunction "CATHODE_2") (pintype "passive"))
      (node (ref "R17") (pin "1") (pinfunction "1_1") (pintype "passive"))
    )
    (net (code "53") (name "Net-(D4-CATHODE)") (class "Default")
      (node (ref "D4") (pin "2") (pinfunction "CATHODE_2") (pintype "passive"))
      (node (ref "R19") (pin "1") (pinfunction "1_1") (pintype "passive"))
    )
    (net (code "54") (name "Net-(D5-CATHODE)") (class "Default")
      (node (ref "D5") (pin "2") (pinfunction "CATHODE_2") (pintype "passive"))
      (node (ref "R20") (pin "1") (pinfunction "1_1") (pintype "passive"))
    )
    (net (code "55") (name "Net-(D6-A)") (class "Default")
      (node (ref "D6") (pin "1") (pinfunction "A_1") (pintype "passive"))
      (node (ref "LS1") (pin "2") (pinfunction "2_2") (pintype "passive"))
      (node (ref "Q6") (pin "3") (pinfunction "C_3") (pintype "passive"))
    )
    (net (code "56") (name "Net-(D8-ANODE)") (class "Default")
      (node (ref "C34") (pin "2") (pinfunction "2_2") (pintype "passive"))
      (node (ref "D8") (pin "1") (pinfunction "ANODE_1") (pintype "passive"))
    )
    (net (code "57") (name "Net-(D9-CATHODE)") (class "Default")
      (node (ref "D9") (pin "2") (pinfunction "CATHODE_2") (pintype "passive"))
      (node (ref "U9") (pin "3") (pinfunction "IN_3") (pintype "passive"))
    )
    (net (code "58") (name "Net-(Q1-B)") (class "Default")
      (node (ref "Q1") (pin "1") (pinfunction "B_1") (pintype "passive"))
      (node (ref "R1") (pin "2") (pinfunction "2_2") (pintype "passive"))
      (node (ref "R3") (pin "1") (pinfunction "1_1") (pintype "passive"))
    )
    (net (code "59") (name "Net-(Q2-G)") (class "Default")
      (node (ref "Q2") (pin "1") (pinfunction "G_1") (pintype "passive"))
      (node (ref "Q3") (pin "3") (pinfunction "C_3") (pintype "passive"))
      (node (ref "R12") (pin "1") (pinfunction "1_1") (pintype "passive"))
    )
    (net (code "60") (name "Net-(Q3-B)") (class "Default")
      (node (ref "Q3") (pin "1") (pinfunction "B_1") (pintype "passive"))
      (node (ref "R13") (pin "2") (pinfunction "2_2") (pintype "passive"))
      (node (ref "R14") (pin "1") (pinfunction "1_1") (pintype "passive"))
    )
    (net (code "61") (name "Net-(Q4-G)") (class "Default")
      (node (ref "Q4") (pin "1") (pinfunction "G_1") (pintype "passive"))
      (node (ref "Q5") (pin "3") (pinfunction "C_3") (pintype "passive"))
      (node (ref "R15") (pin "1") (pinfunction "1_1") (pintype "passive"))
    )
    (net (code "62") (name "Net-(Q5-B)") (class "Default")
      (node (ref "Q5") (pin "1") (pinfunction "B_1") (pintype "passive"))
      (node (ref "R16") (pin "2") (pinfunction "2_2") (pintype "passive"))
      (node (ref "R18") (pin "1") (pinfunction "1_1") (pintype "passive"))
    )
    (net (code "63") (name "Net-(Q6-B)") (class "Default")
      (node (ref "Q6") (pin "1") (pinfunction "B_1") (pintype "passive"))
      (node (ref "R28") (pin "2") (pinfunction "2_2") (pintype "passive"))
      (node (ref "R31") (pin "1") (pinfunction "1_1") (pintype "passive"))
    )
    (net (code "64") (name "Net-(U3-CLK)") (class "Default")
      (node (ref "R7") (pin "2") (pinfunction "2_2") (pintype "passive"))
      (node (ref "U3") (pin "3") (pinfunction "CLK_3") (pintype "passive"))
    )
    (net (code "65") (name "Net-(U3-IO)") (class "Default")
      (node (ref "R10") (pin "2") (pinfunction "2_2") (pintype "passive"))
      (node (ref "R11") (pin "2") (pinfunction "2_2") (pintype "passive"))
      (node (ref "U3") (pin "6") (pinfunction "IO_6") (pintype "passive"))
    )
    (net (code "66") (name "Net-(U3-RST)") (class "Default")
      (node (ref "R8") (pin "2") (pinfunction "2_2") (pintype "passive"))
      (node (ref "U3") (pin "2") (pinfunction "RST_2") (pintype "passive"))
    )
    (net (code "67") (name "Net-(U4-BOOT0)") (class "Default")
      (node (ref "R29") (pin "2") (pinfunction "2_2") (pintype "passive"))
      (node (ref "U4") (pin "44") (pinfunction "BOOT0_44") (pintype "input"))
    )
    (net (code "68") (name "Net-(U4-OSC_IN{slash}PD0)") (class "Default")
      (node (ref "C13") (pin "2") (pinfunction "2_2") (pintype "passive"))
      (node (ref "U4") (pin "5") (pinfunction "OSC_IN/PD0_5") (pintype "input"))
      (node (ref "X1") (pin "3") (pinfunction "3_3") (pintype "passive"))
    )
    (net (code "69") (name "Net-(U4-OSC_OUT{slash}PD1)") (class "Default")
      (node (ref "C15") (pin "2") (pinfunction "2_2") (pintype "passive"))
      (node (ref "U4") (pin "6") (pinfunction "OSC_OUT/PD1_6") (pintype "output"))
      (node (ref "X1") (pin "1") (pinfunction "1_1") (pintype "passive"))
    )
    (net (code "70") (name "Net-(U4-PB2{slash}BOOT1)") (class "Default")
      (node (ref "R24") (pin "1") (pinfunction "1_1") (pintype "passive"))
      (node (ref "U4") (pin "20") (pinfunction "PB2/BOOT1_20") (pintype "bidirectional"))
    )
    (net (code "71") (name "Net-(U4-PC14-OSC32_IN)") (class "Default")
      (node (ref "C14") (pin "1") (pinfunction "1_1") (pintype "passive"))
      (node (ref "U4") (pin "3") (pinfunction "PC14-OSC32_IN_3") (pintype "bidirectional"))
      (node (ref "X2") (pin "2") (pinfunction "2_2") (pintype "passive"))
    )
    (net (code "72") (name "Net-(U4-PC15-OSC32_OUT)") (class "Default")
      (node (ref "C16") (pin "1") (pinfunction "1_1") (pintype "passive"))
      (node (ref "U4") (pin "4") (pinfunction "PC15-OSC32_OUT_4") (pintype "bidirectional"))
      (node (ref "X2") (pin "1") (pinfunction "1_1") (pintype "passive"))
    )
    (net (code "73") (name "Net-(U4-VBAT)") (class "Default")
      (node (ref "C17") (pin "1") (pinfunction "1_1") (pintype "passive"))
      (node (ref "D7") (pin "2") (pintype "passive"))
      (node (ref "U4") (pin "1") (pinfunction "VBAT_1") (pintype "power_in"))
    )
    (net (code "74") (name "Net-(U4-VDDA)") (class "Default")
      (node (ref "C20") (pin "2") (pinfunction "2_2") (pintype "passive"))
      (node (ref "C21") (pin "2") (pinfunction "2_2") (pintype "passive"))
      (node (ref "R39") (pin "2") (pinfunction "2_2") (pintype "passive"))
      (node (ref "U4") (pin "9") (pinfunction "VDDA_9") (pintype "power_in"))
    )
    (net (code "75") (name "Net-(U5-RXD)") (class "Default")
      (node (ref "R26") (pin "2") (pinfunction "2_2") (pintype "passive"))
      (node (ref "U5") (pin "3") (pinfunction "RXD_3") (pintype "passive"))
    )
    (net (code "76") (name "Net-(U5-TXD)") (class "Default")
      (node (ref "R25") (pin "2") (pinfunction "2_2") (pintype "passive"))
      (node (ref "U5") (pin "2") (pinfunction "TXD_2") (pintype "passive"))
    )
    (net (code "77") (name "Net-(U5-V3)") (class "Default")
      (node (ref "C12") (pin "1") (pinfunction "1_1") (pintype "passive"))
      (node (ref "U5") (pin "4") (pinfunction "V3_4") (pintype "passive"))
    )
    (net (code "78") (name "Net-(U6-C1N)") (class "Default")
      (node (ref "C26") (pin "2") (pinfunction "2_2") (pintype "passive"))
      (node (ref "U6") (pin "5") (pinfunction "C1N_5") (pintype "passive"))
    )
    (net (code "79") (name "Net-(U6-C1P)") (class "Default")
      (node (ref "C26") (pin "1") (pinfunction "1_1") (pintype "passive"))
      (node (ref "U6") (pin "4") (pinfunction "C1P_4") (pintype "passive"))
    )
    (net (code "80") (name "Net-(U6-C2N)") (class "Default")
      (node (ref "C25") (pin "2") (pinfunction "2_2") (pintype "passive"))
      (node (ref "U6") (pin "3") (pinfunction "C2N_3") (pintype "passive"))
    )
    (net (code "81") (name "Net-(U6-C2P)") (class "Default")
      (node (ref "C25") (pin "1") (pinfunction "1_1") (pintype "passive"))
      (node (ref "U6") (pin "2") (pinfunction "C2P_2") (pintype "passive"))
    )
    (net (code "82") (name "Net-(U6-IREF)") (class "Default")
      (node (ref "R27") (pin "1") (pinfunction "1_1") (pintype "passive"))
      (node (ref "U6") (pin "26") (pinfunction "IREF_26") (pintype "passive"))
    )
    (net (code "83") (name "Net-(U6-RES#)") (class "Default")
      (node (ref "R40") (pin "1") (pinfunction "1_1") (pintype "passive"))
      (node (ref "U6") (pin "14") (pinfunction "RES#_14") (pintype "passive"))
    )
    (net (code "84") (name "Net-(U6-VCC)") (class "Default")
      (node (ref "C29") (pin "2") (pinfunction "2_2") (pintype "passive"))
      (node (ref "C30") (pin "2") (pinfunction "2_2") (pintype "passive"))
      (node (ref "U6") (pin "28") (pinfunction "VCC_28") (pintype "passive"))
    )
    (net (code "85") (name "Net-(U6-VCOMH)") (class "Default")
      (node (ref "C28") (pin "2") (pinfunction "2_2") (pintype "passive"))
      (node (ref "U6") (pin "27") (pinfunction "VCOMH_27") (pintype "passive"))
    )
    (net (code "86") (name "VCC_5V") (class "Default")
      (node (ref "C10") (pin "1") (pinfunction "1_1") (pintype "passive"))
      (node (ref "C22") (pin "1") (pinfunction "1_1") (pintype "passive"))
      (node (ref "C23") (pin "2") (pinfunction "2_2") (pintype "passive"))
      (node (ref "U5") (pin "16") (pinfunction "VCC_16") (pintype "passive"))
      (node (ref "U7") (pin "3") (pinfunction "IN_3") (pintype "passive"))
      (node (ref "U9") (pin "4") (pinfunction "OUT_4") (pintype "passive"))
      (node (ref "USB1") (pin "1") (pinfunction "+5V_1") (pintype "passive"))
    )
    (net (code "87") (name "VCC_BLUE") (class "Default")
      (node (ref "C4") (pin "2") (pinfunction "2_2") (pintype "passive"))
      (node (ref "Q2") (pin "3") (pinfunction "D_3") (pintype "passive"))
      (node (ref "U1") (pin "12") (pinfunction "VCC_12") (pintype "passive"))
    )
    (net (code "88") (name "VCC_NB") (class "Default")
      (node (ref "C8") (pin "1") (pinfunction "1_1") (pintype "passive"))
      (node (ref "Q4") (pin "3") (pinfunction "D_3") (pintype "passive"))
      (node (ref "U2") (pin "45") (pinfunction "VBAT_45") (pintype "passive"))
      (node (ref "U2") (pin "46") (pinfunction "VBAT_46") (pintype "passive"))
    )
    (net (code "89") (name "unconnected-(U1-DC-Pad6)") (class "Default")
      (node (ref "U1") (pin "6") (pinfunction "DC_6") (pintype "passive"))
    )
    (net (code "90") (name "unconnected-(U1-DD-Pad7)") (class "Default")
      (node (ref "U1") (pin "7") (pinfunction "DD_7") (pintype "passive"))
    )
    (net (code "91") (name "unconnected-(U1-GND-Pad28)") (class "Default")
      (node (ref "U1") (pin "28") (pinfunction "GND_28") (pintype "passive"))
    )
    (net (code "92") (name "unconnected-(U1-NC-Pad3)") (class "Default")
      (node (ref "U1") (pin "3") (pinfunction "NC_3") (pintype "passive"))
    )
    (net (code "93") (name "unconnected-(U1-NC-Pad4)") (class "Default")
      (node (ref "U1") (pin "4") (pinfunction "NC_4") (pintype "passive"))
    )
    (net (code "94") (name "unconnected-(U1-NC-Pad5)") (class "Default")
      (node (ref "U1") (pin "5") (pinfunction "NC_5") (pintype "passive"))
    )
    (net (code "95") (name "unconnected-(U1-P0.0-Pad26)") (class "Default")
      (node (ref "U1") (pin "26") (pinfunction "P0.0_26") (pintype "passive"))
    )
    (net (code "96") (name "unconnected-(U1-P0.1-Pad24)") (class "Default")
      (node (ref "U1") (pin "24") (pinfunction "P0.1_24") (pintype "passive"))
    )
    (net (code "97") (name "unconnected-(U1-P0.6-Pad23)") (class "Default")
      (node (ref "U1") (pin "23") (pinfunction "P0.6_23") (pintype "passive"))
    )
    (net (code "98") (name "unconnected-(U1-P0.7-Pad20)") (class "Default")
      (node (ref "U1") (pin "20") (pinfunction "P0.7_20") (pintype "passive"))
    )
    (net (code "99") (name "unconnected-(U1-P1.0-Pad19)") (class "Default")
      (node (ref "U1") (pin "19") (pinfunction "P1.0_19") (pintype "passive"))
    )
    (net (code "100") (name "unconnected-(U1-P1.4-Pad15)") (class "Default")
      (node (ref "U1") (pin "15") (pinfunction "P1.4_15") (pintype "passive"))
    )
    (net (code "101") (name "unconnected-(U1-P1.5-Pad25)") (class "Default")
      (node (ref "U1") (pin "25") (pinfunction "P1.5_25") (pintype "passive"))
    )
    (net (code "102") (name "unconnected-(U1-P1.6-Pad10)") (class "Default")
      (node (ref "U1") (pin "10") (pinfunction "P1.6_10") (pintype "passive"))
    )
    (net (code "103") (name "unconnected-(U1-P1.7-Pad9)") (class "Default")
      (node (ref "U1") (pin "9") (pinfunction "P1.7_9") (pintype "passive"))
    )
    (net (code "104") (name "unconnected-(U1-P2.0-Pad8)") (class "Default")
      (node (ref "U1") (pin "8") (pinfunction "P2.0_8") (pintype "passive"))
    )
    (net (code "105") (name "unconnected-(U1-RXD-Pad29)") (class "Default")
      (node (ref "U1") (pin "29") (pinfunction "RXD_29") (pintype "passive"))
    )
    (net (code "106") (name "unconnected-(U1-TXD-Pad30)") (class "Default")
      (node (ref "U1") (pin "30") (pinfunction "TXD_30") (pintype "passive"))
    )
    (net (code "107") (name "unconnected-(U1-USB_D+-Pad22)") (class "Default")
      (node (ref "U1") (pin "22") (pinfunction "USB_D+_22") (pintype "passive"))
    )
    (net (code "108") (name "unconnected-(U1-USB_D--Pad21)") (class "Default")
      (node (ref "U1") (pin "21") (pinfunction "USB_D-_21") (pintype "passive"))
    )
    (net (code "109") (name "unconnected-(U1-VCC-Pad27)") (class "Default")
      (node (ref "U1") (pin "27") (pinfunction "VCC_27") (pintype "passive"))
    )
    (net (code "110") (name "unconnected-(U2A-ADC-Pad21)") (class "Default")
      (node (ref "U2") (pin "21") (pinfunction "ADC_21") (pintype "passive"))
    )
    (net (code "111") (name "unconnected-(U2A-DBG_RXD-Pad19)") (class "Default")
      (node (ref "U2") (pin "19") (pinfunction "DBG_RXD_19") (pintype "passive"))
    )
    (net (code "112") (name "unconnected-(U2A-DBG_TXD-Pad20)") (class "Default")
      (node (ref "U2") (pin "20") (pinfunction "DBG_TXD_20") (pintype "passive"))
    )
    (net (code "113") (name "unconnected-(U2A-NETLIGHT-Pad18)") (class "Default")
      (node (ref "U2") (pin "18") (pinfunction "NETLIGHT_18") (pintype "passive"))
    )
    (net (code "114") (name "unconnected-(U2A-RESERVED-Pad1)") (class "Default")
      (node (ref "U2") (pin "1") (pinfunction "RESERVED_1") (pintype "passive"))
    )
    (net (code "115") (name "unconnected-(U2A-RESERVED-Pad3)") (class "Default")
      (node (ref "U2") (pin "3") (pinfunction "RESERVED_3") (pintype "passive"))
    )
    (net (code "116") (name "unconnected-(U2A-RESERVED-Pad4)") (class "Default")
      (node (ref "U2") (pin "4") (pinfunction "RESERVED_4") (pintype "passive"))
    )
    (net (code "117") (name "unconnected-(U2A-RESERVED-Pad5)") (class "Default")
      (node (ref "U2") (pin "5") (pinfunction "RESERVED_5") (pintype "passive"))
    )
    (net (code "118") (name "unconnected-(U2A-RESERVED-Pad6)") (class "Default")
      (node (ref "U2") (pin "6") (pinfunction "RESERVED_6") (pintype "passive"))
    )
    (net (code "119") (name "unconnected-(U2A-RESERVED-Pad7)") (class "Default")
      (node (ref "U2") (pin "7") (pinfunction "RESERVED_7") (pintype "passive"))
    )
    (net (code "120") (name "unconnected-(U2A-RESERVED-Pad8)") (class "Default")
      (node (ref "U2") (pin "8") (pinfunction "RESERVED_8") (pintype "passive"))
    )
    (net (code "121") (name "unconnected-(U2A-RESERVED-Pad9)") (class "Default")
      (node (ref "U2") (pin "9") (pinfunction "RESERVED_9") (pintype "passive"))
    )
    (net (code "122") (name "unconnected-(U2A-RESERVED-Pad10)") (class "Default")
      (node (ref "U2") (pin "10") (pinfunction "RESERVED_10") (pintype "passive"))
    )
    (net (code "123") (name "unconnected-(U2A-RESERVED-Pad11)") (class "Default")
      (node (ref "U2") (pin "11") (pinfunction "RESERVED_11") (pintype "passive"))
    )
    (net (code "124") (name "unconnected-(U2A-RESERVED-Pad12)") (class "Default")
      (node (ref "U2") (pin "12") (pinfunction "RESERVED_12") (pintype "passive"))
    )
    (net (code "125") (name "unconnected-(U2A-RESERVED-Pad13)") (class "Default")
      (node (ref "U2") (pin "13") (pinfunction "RESERVED_13") (pintype "passive"))
    )
    (net (code "126") (name "unconnected-(U2A-RESERVED-Pad14)") (class "Default")
      (node (ref "U2") (pin "14") (pinfunction "RESERVED_14") (pintype "passive"))
    )
    (net (code "127") (name "unconnected-(U2A-RESERVED-Pad16)") (class "Default")
      (node (ref "U2") (pin "16") (pinfunction "RESERVED_16") (pintype "passive"))
    )
    (net (code "128") (name "unconnected-(U2A-RESERVED-Pad17)") (class "Default")
      (node (ref "U2") (pin "17") (pinfunction "RESERVED_17") (pintype "passive"))
    )
    (net (code "129") (name "unconnected-(U2A-RESERVED-Pad22)") (class "Default")
      (node (ref "U2") (pin "22") (pinfunction "RESERVED_22") (pintype "passive"))
    )
    (net (code "130") (name "unconnected-(U2A-RESERVED-Pad23)") (class "Default")
      (node (ref "U2") (pin "23") (pinfunction "RESERVED_23") (pintype "passive"))
    )
    (net (code "131") (name "unconnected-(U2A-RESERVED-Pad24)") (class "Default")
      (node (ref "U2") (pin "24") (pinfunction "RESERVED_24") (pintype "passive"))
    )
    (net (code "132") (name "unconnected-(U2A-RESERVED-Pad25)") (class "Default")
      (node (ref "U2") (pin "25") (pinfunction "RESERVED_25") (pintype "passive"))
    )
    (net (code "133") (name "unconnected-(U2A-RESERVED-Pad27)") (class "Default")
      (node (ref "U2") (pin "27") (pinfunction "RESERVED_27") (pintype "passive"))
    )
    (net (code "134") (name "unconnected-(U2A-RESERVED-Pad28)") (class "Default")
      (node (ref "U2") (pin "28") (pinfunction "RESERVED_28") (pintype "passive"))
    )
    (net (code "135") (name "unconnected-(U2A-RESERVED-Pad31)") (class "Default")
      (node (ref "U2") (pin "31") (pinfunction "RESERVED_31") (pintype "passive"))
    )
    (net (code "136") (name "unconnected-(U2A-RESERVED-Pad32)") (class "Default")
      (node (ref "U2") (pin "32") (pinfunction "RESERVED_32") (pintype "passive"))
    )
    (net (code "137") (name "unconnected-(U2A-RESERVED-Pad33)") (class "Default")
      (node (ref "U2") (pin "33") (pinfunction "RESERVED_33") (pintype "passive"))
    )
    (net (code "138") (name "unconnected-(U2A-RESERVED-Pad35)") (class "Default")
      (node (ref "U2") (pin "35") (pinfunction "RESERVED_35") (pintype "passive"))
    )
    (net (code "139") (name "unconnected-(U2A-RESERVED-Pad36)") (class "Default")
      (node (ref "U2") (pin "36") (pinfunction "RESERVED_36") (pintype "passive"))
    )
    (net (code "140") (name "unconnected-(U2A-RESERVED-Pad37)") (class "Default")
      (node (ref "U2") (pin "37") (pinfunction "RESERVED_37") (pintype "passive"))
    )
    (net (code "141") (name "unconnected-(U2A-RESERVED-Pad44)") (class "Default")
      (node (ref "U2") (pin "44") (pinfunction "RESERVED_44") (pintype "passive"))
    )
    (net (code "142") (name "unconnected-(U2A-RESERVED-Pad49)") (class "Default")
      (node (ref "U2") (pin "49") (pinfunction "RESERVED_49") (pintype "passive"))
    )
    (net (code "143") (name "unconnected-(U2A-RESERVED-Pad50)") (class "Default")
      (node (ref "U2") (pin "50") (pinfunction "RESERVED_50") (pintype "passive"))
    )
    (net (code "144") (name "unconnected-(U2A-RI-Pad34)") (class "Default")
      (node (ref "U2") (pin "34") (pinfunction "RI_34") (pintype "passive"))
    )
    (net (code "145") (name "unconnected-(U2A-VDD_EXT-Pad26)") (class "Default")
      (node (ref "U2") (pin "26") (pinfunction "VDD_EXT_26") (pintype "passive"))
    )
    (net (code "146") (name "unconnected-(U3-VPP-Pad5)") (class "Default")
      (node (ref "U3") (pin "5") (pinfunction "VPP_5") (pintype "passive"))
    )
    (net (code "147") (name "unconnected-(U4-PA15{slash}JTDI-Pad38)") (class "Default")
      (node (ref "U4") (pin "38") (pinfunction "PA15/JTDI_38") (pintype "bidirectional"))
    )
    (net (code "148") (name "unconnected-(U4-PB0-Pad18)") (class "Default")
      (node (ref "U4") (pin "18") (pinfunction "PB0_18") (pintype "bidirectional"))
    )
    (net (code "149") (name "unconnected-(U4-PB1-Pad19)") (class "Default")
      (node (ref "U4") (pin "19") (pinfunction "PB1_19") (pintype "bidirectional"))
    )
    (net (code "150") (name "unconnected-(U4-PB15-Pad28)") (class "Default")
      (node (ref "U4") (pin "28") (pinfunction "PB15_28") (pintype "bidirectional"))
    )
    (net (code "151") (name "unconnected-(U4-PC13-TAMPER-RTC-Pad2)") (class "Default")
      (node (ref "U4") (pin "2") (pinfunction "PC13-TAMPER-RTC_2") (pintype "bidirectional"))
    )
    (net (code "152") (name "unconnected-(U5-CTS-Pad9)") (class "Default")
      (node (ref "U5") (pin "9") (pinfunction "CTS_9") (pintype "passive"))
    )
    (net (code "153") (name "unconnected-(U5-DSR-Pad10)") (class "Default")
      (node (ref "U5") (pin "10") (pinfunction "DSR_10") (pintype "passive"))
    )
    (net (code "154") (name "unconnected-(U5-DTR-Pad13)") (class "Default")
      (node (ref "U5") (pin "13") (pinfunction "DTR_13") (pintype "passive"))
    )
    (net (code "155") (name "unconnected-(U5-R233-Pad15)") (class "Default")
      (node (ref "U5") (pin "15") (pinfunction "R233_15") (pintype "passive"))
    )
    (net (code "156") (name "unconnected-(U5-RCD-Pad12)") (class "Default")
      (node (ref "U5") (pin "12") (pinfunction "RCD_12") (pintype "passive"))
    )
    (net (code "157") (name "unconnected-(U5-RI-Pad11)") (class "Default")
      (node (ref "U5") (pin "11") (pinfunction "RI_11") (pintype "passive"))
    )
    (net (code "158") (name "unconnected-(U5-RTS-Pad14)") (class "Default")
      (node (ref "U5") (pin "14") (pinfunction "RTS_14") (pintype "passive"))
    )
    (net (code "159") (name "unconnected-(U5-XD-Pad8)") (class "Default")
      (node (ref "U5") (pin "8") (pinfunction "XD_8") (pintype "passive"))
    )
    (net (code "160") (name "unconnected-(U5-XI-Pad7)") (class "Default")
      (node (ref "U5") (pin "7") (pinfunction "XI_7") (pintype "passive"))
    )
    (net (code "161") (name "unconnected-(U6-D2-Pad20)") (class "Default")
      (node (ref "U6") (pin "20") (pinfunction "D2_20") (pintype "passive+no_connect"))
    )
    (net (code "162") (name "unconnected-(U9-OUT-Pad2)") (class "Default")
      (node (ref "U9") (pin "2") (pinfunction "OUT_2") (pintype "passive"))
    )
    (net (code "163") (name "unconnected-(X1-Pad2)") (class "Default")
      (node (ref "X1") (pin "2") (pinfunction "2_2") (pintype "passive"))
    )
    (net (code "164") (name "unconnected-(X1-Pad4)") (class "Default")
      (node (ref "X1") (pin "4") (pinfunction "4_4") (pintype "passive"))
    )
  )
)
